# USB_Adapter_V1.net
KiCad netlist of a schematic drawn in EAGLE
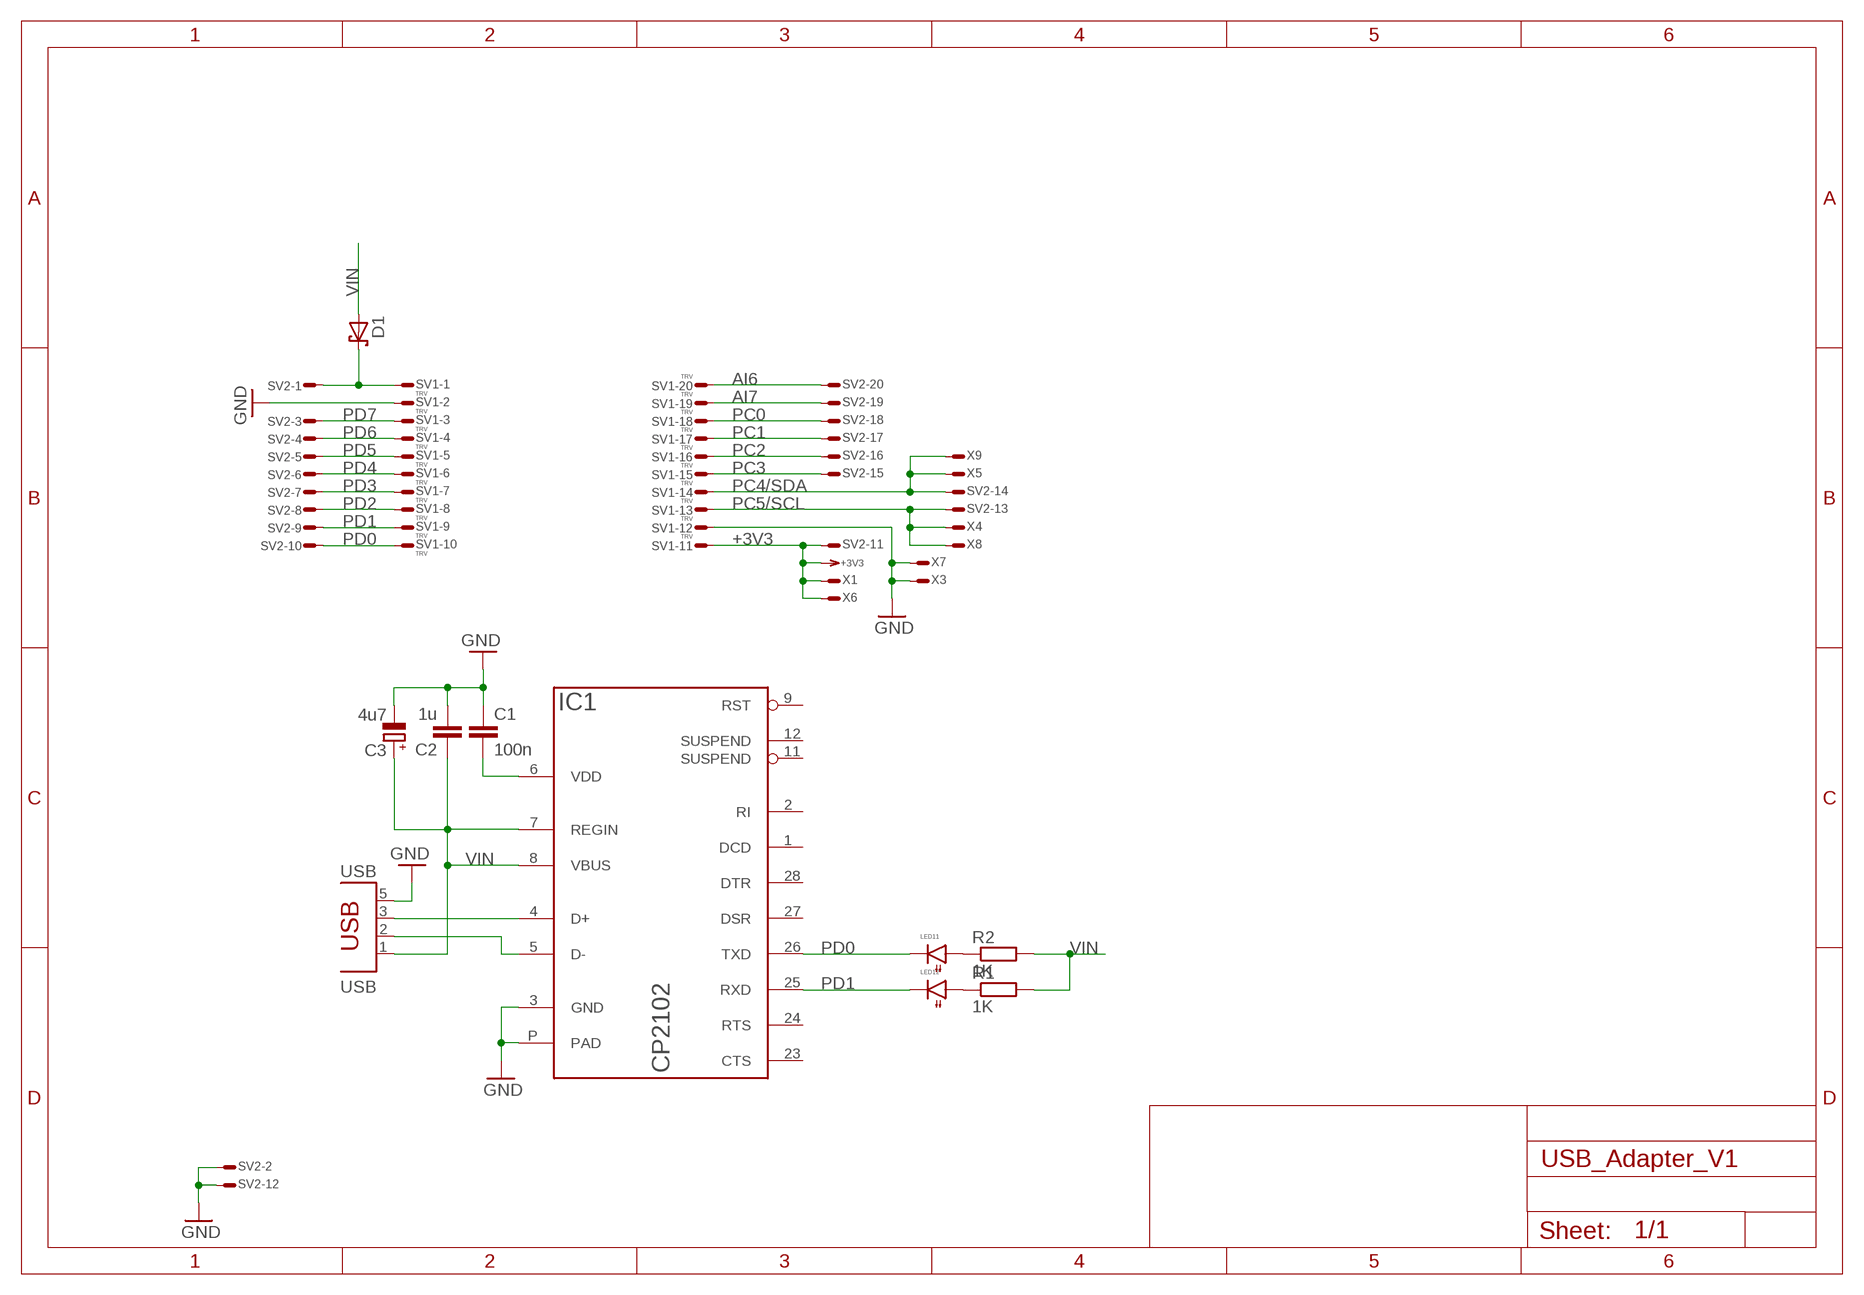
[diagram p0: schematic, sheet 1]

(export (version "E")
  (design (tool "Eeschema 10.0.6"))
  (components
    (comp (ref "C1")
      (value "100n")
      (footprint "eagle-import:0603")
      (libsource (lib "eagle-import") (part "C0603"))
    )
    (comp (ref "C2")
      (value "1u")
      (footprint "eagle-import:0603")
      (libsource (lib "eagle-import") (part "C0603"))
    )
    (comp (ref "C3")
      (value "4u7")
      (footprint "eagle-import:SMC_A")
      (libsource (lib "eagle-import") (part "C_POLSMCA"))
    )
    (comp (ref "D1")
      (value "D-SCHOTKY323")
      (footprint "eagle-import:SOD323")
      (libsource (lib "eagle-import") (part "D-SCHOTKY323"))
    )
    (comp (ref "IC1")
      (value "CP2102")
      (footprint "eagle-import:QFN28")
      (libsource (lib "eagle-import") (part "CP2102"))
    )
    (comp (ref "LED1")
      (value "2LED3")
      (footprint "eagle-import:HSMF")
      (libsource (lib "eagle-import") (part "2LED3"))
    )
    (comp (ref "R1")
      (value "1K")
      (footprint "eagle-import:0603")
      (libsource (lib "eagle-import") (part "R0603"))
    )
    (comp (ref "R2")
      (value "1K")
      (footprint "eagle-import:0603")
      (libsource (lib "eagle-import") (part "R0603"))
    )
    (comp (ref "SV1")
      (value "TRV")
      (footprint "eagle-import:FE10-2WSS")
      (libsource (lib "eagle-import") (part "FE20ELSS"))
    )
    (comp (ref "SV2")
      (value "ML20SE")
      (footprint "eagle-import:ML20S")
      (libsource (lib "eagle-import") (part "ML20?ES"))
    )
    (comp (ref "USB")
      (value "USB")
      (footprint "eagle-import:USB-BM")
      (libsource (lib "eagle-import") (part "USBBM"))
    )
    (comp (ref "X1")
      (value "WIREPADT1.6/0.9")
      (footprint "eagle-import:T1.6_0.9")
      (libsource (lib "eagle-import") (part "WIREPADT1.6/0.9"))
    )
    (comp (ref "X3")
      (value "WIREPADT1.6/0.9")
      (footprint "eagle-import:T1.6_0.9")
      (libsource (lib "eagle-import") (part "WIREPADT1.6/0.9"))
    )
    (comp (ref "X4")
      (value "WIREPADT1.6/0.9")
      (footprint "eagle-import:T1.6_0.9")
      (libsource (lib "eagle-import") (part "WIREPADT1.6/0.9"))
    )
    (comp (ref "X5")
      (value "WIREPADT1.6/0.9")
      (footprint "eagle-import:T1.6_0.9")
      (libsource (lib "eagle-import") (part "WIREPADT1.6/0.9"))
    )
    (comp (ref "X6")
      (value "WIREPADT1.6/0.9")
      (footprint "eagle-import:T1.6_0.9")
      (libsource (lib "eagle-import") (part "WIREPADT1.6/0.9"))
    )
    (comp (ref "X7")
      (value "WIREPADT1.6/0.9")
      (footprint "eagle-import:T1.6_0.9")
      (libsource (lib "eagle-import") (part "WIREPADT1.6/0.9"))
    )
    (comp (ref "X8")
      (value "WIREPADT1.6/0.9")
      (footprint "eagle-import:T1.6_0.9")
      (libsource (lib "eagle-import") (part "WIREPADT1.6/0.9"))
    )
    (comp (ref "X9")
      (value "WIREPADT1.6/0.9")
      (footprint "eagle-import:T1.6_0.9")
      (libsource (lib "eagle-import") (part "WIREPADT1.6/0.9"))
    )
  )
  (nets
    (net (code "1") (name "+3V3") (class "Default")
      (node (ref "SV1") (pin "P$11") (pinfunction "S_P$11") (pintype "passive"))
      (node (ref "SV2") (pin "11") (pinfunction "S_11") (pintype "passive"))
      (node (ref "X1") (pin "1") (pinfunction "S_1") (pintype "passive"))
      (node (ref "X6") (pin "1") (pinfunction "S_1") (pintype "passive"))
    )
    (net (code "2") (name "/AI6") (class "Default")
      (node (ref "SV1") (pin "P$20") (pinfunction "S_P$20") (pintype "passive"))
      (node (ref "SV2") (pin "20") (pinfunction "S_20") (pintype "passive"))
    )
    (net (code "3") (name "/AI7") (class "Default")
      (node (ref "SV1") (pin "P$19") (pinfunction "S_P$19") (pintype "passive"))
      (node (ref "SV2") (pin "19") (pinfunction "S_19") (pintype "passive"))
    )
    (net (code "4") (name "/PC0") (class "Default")
      (node (ref "SV1") (pin "P$18") (pinfunction "S_P$18") (pintype "passive"))
      (node (ref "SV2") (pin "18") (pinfunction "S_18") (pintype "passive"))
    )
    (net (code "5") (name "/PC1") (class "Default")
      (node (ref "SV1") (pin "P$17") (pinfunction "S_P$17") (pintype "passive"))
      (node (ref "SV2") (pin "17") (pinfunction "S_17") (pintype "passive"))
    )
    (net (code "6") (name "/PC2") (class "Default")
      (node (ref "SV1") (pin "P$16") (pinfunction "S_P$16") (pintype "passive"))
      (node (ref "SV2") (pin "16") (pinfunction "S_16") (pintype "passive"))
    )
    (net (code "7") (name "/PC3") (class "Default")
      (node (ref "SV1") (pin "P$15") (pinfunction "S_P$15") (pintype "passive"))
      (node (ref "SV2") (pin "15") (pinfunction "S_15") (pintype "passive"))
    )
    (net (code "8") (name "/PC4{slash}SDA") (class "Default")
      (node (ref "SV1") (pin "P$14") (pinfunction "S_P$14") (pintype "passive"))
      (node (ref "SV2") (pin "14") (pinfunction "S_14") (pintype "passive"))
      (node (ref "X5") (pin "1") (pinfunction "S_1") (pintype "passive"))
      (node (ref "X9") (pin "1") (pinfunction "S_1") (pintype "passive"))
    )
    (net (code "9") (name "/PC5{slash}SCL") (class "Default")
      (node (ref "SV1") (pin "P$13") (pinfunction "S_P$13") (pintype "passive"))
      (node (ref "SV2") (pin "13") (pinfunction "S_13") (pintype "passive"))
      (node (ref "X4") (pin "1") (pinfunction "S_1") (pintype "passive"))
      (node (ref "X8") (pin "1") (pinfunction "S_1") (pintype "passive"))
    )
    (net (code "10") (name "/PD0") (class "Default")
      (node (ref "IC1") (pin "26") (pinfunction "TXD_26") (pintype "output"))
      (node (ref "LED1") (pin "2") (pinfunction "C_2") (pintype "bidirectional"))
      (node (ref "SV1") (pin "P$10") (pinfunction "S_P$10") (pintype "passive"))
      (node (ref "SV2") (pin "10") (pinfunction "S_10") (pintype "passive"))
    )
    (net (code "11") (name "/PD1") (class "Default")
      (node (ref "IC1") (pin "25") (pinfunction "RXD_25") (pintype "input"))
      (node (ref "LED1") (pin "4") (pinfunction "C_4") (pintype "bidirectional"))
      (node (ref "SV1") (pin "P$9") (pinfunction "S_P$9") (pintype "passive"))
      (node (ref "SV2") (pin "9") (pinfunction "S_9") (pintype "passive"))
    )
    (net (code "12") (name "/PD2") (class "Default")
      (node (ref "SV1") (pin "P$8") (pinfunction "S_P$8") (pintype "passive"))
      (node (ref "SV2") (pin "8") (pinfunction "S_8") (pintype "passive"))
    )
    (net (code "13") (name "/PD3") (class "Default")
      (node (ref "SV1") (pin "P$7") (pinfunction "S_P$7") (pintype "passive"))
      (node (ref "SV2") (pin "7") (pinfunction "S_7") (pintype "passive"))
    )
    (net (code "14") (name "/PD4") (class "Default")
      (node (ref "SV1") (pin "P$6") (pinfunction "S_P$6") (pintype "passive"))
      (node (ref "SV2") (pin "6") (pinfunction "S_6") (pintype "passive"))
    )
    (net (code "15") (name "/PD5") (class "Default")
      (node (ref "SV1") (pin "P$5") (pinfunction "S_P$5") (pintype "passive"))
      (node (ref "SV2") (pin "5") (pinfunction "S_5") (pintype "passive"))
    )
    (net (code "16") (name "/PD6") (class "Default")
      (node (ref "SV1") (pin "P$4") (pinfunction "S_P$4") (pintype "passive"))
      (node (ref "SV2") (pin "4") (pinfunction "S_4") (pintype "passive"))
    )
    (net (code "17") (name "/PD7") (class "Default")
      (node (ref "SV1") (pin "P$3") (pinfunction "S_P$3") (pintype "passive"))
      (node (ref "SV2") (pin "3") (pinfunction "S_3") (pintype "passive"))
    )
    (net (code "18") (name "/VIN") (class "Default")
      (node (ref "C2") (pin "1") (pinfunction "1_1") (pintype "passive"))
      (node (ref "C3") (pin "+") (pinfunction "+_+") (pintype "passive"))
      (node (ref "D1") (pin "A") (pinfunction "A_A") (pintype "passive"))
      (node (ref "IC1") (pin "7") (pinfunction "REGIN_7") (pintype "input"))
      (node (ref "IC1") (pin "8") (pinfunction "VBUS_8") (pintype "input"))
      (node (ref "R1") (pin "2") (pinfunction "2_2") (pintype "passive"))
      (node (ref "R2") (pin "2") (pinfunction "2_2") (pintype "passive"))
      (node (ref "USB") (pin "1") (pinfunction "VCC_1") (pintype "bidirectional"))
    )
    (net (code "19") (name "GND") (class "Default")
      (node (ref "C1") (pin "1") (pinfunction "1_1") (pintype "passive"))
      (node (ref "C2") (pin "2") (pinfunction "2_2") (pintype "passive"))
      (node (ref "C3") (pin "-") (pinfunction "-_-") (pintype "passive"))
      (node (ref "IC1") (pin "3") (pinfunction "GND_3") (pintype "power_in"))
      (node (ref "IC1") (pin "P") (pinfunction "PAD_P") (pintype "power_in"))
      (node (ref "SV1") (pin "P$12") (pinfunction "S_P$12") (pintype "passive"))
      (node (ref "SV1") (pin "P$2") (pinfunction "S_P$2") (pintype "passive"))
      (node (ref "SV2") (pin "12") (pinfunction "S_12") (pintype "passive"))
      (node (ref "SV2") (pin "2") (pinfunction "S_2") (pintype "passive"))
      (node (ref "USB") (pin "5") (pinfunction "GND_5") (pintype "bidirectional"))
      (node (ref "X3") (pin "1") (pinfunction "S_1") (pintype "passive"))
      (node (ref "X7") (pin "1") (pinfunction "S_1") (pintype "passive"))
    )
    (net (code "20") (name "Net-(IC1-D+)") (class "Default")
      (node (ref "IC1") (pin "4") (pinfunction "D+_4") (pintype "bidirectional"))
      (node (ref "USB") (pin "3") (pinfunction "D+_3") (pintype "bidirectional"))
    )
    (net (code "21") (name "Net-(IC1-D-)") (class "Default")
      (node (ref "IC1") (pin "5") (pinfunction "D-_5") (pintype "bidirectional"))
      (node (ref "USB") (pin "2") (pinfunction "D-_2") (pintype "bidirectional"))
    )
    (net (code "22") (name "Net-(IC1-VDD)") (class "Default")
      (node (ref "C1") (pin "2") (pinfunction "2_2") (pintype "passive"))
      (node (ref "IC1") (pin "6") (pinfunction "VDD_6") (pintype "passive"))
    )
    (net (code "23") (name "Net-(LED1A-A)") (class "Default")
      (node (ref "LED1") (pin "1") (pinfunction "A_1") (pintype "bidirectional"))
      (node (ref "R2") (pin "1") (pinfunction "1_1") (pintype "passive"))
    )
    (net (code "24") (name "Net-(LED1B-A)") (class "Default")
      (node (ref "LED1") (pin "3") (pinfunction "A_3") (pintype "bidirectional"))
      (node (ref "R1") (pin "1") (pinfunction "1_1") (pintype "passive"))
    )
    (net (code "25") (name "Net-(SV1A-S)") (class "Default")
      (node (ref "D1") (pin "C") (pinfunction "C_C") (pintype "passive"))
      (node (ref "SV1") (pin "P$1") (pinfunction "S_P$1") (pintype "passive"))
      (node (ref "SV2") (pin "1") (pinfunction "S_1") (pintype "passive"))
    )
    (net (code "26") (name "unconnected-(IC1-CTS-Pad23)") (class "Default")
      (node (ref "IC1") (pin "23") (pinfunction "CTS_23") (pintype "input"))
    )
    (net (code "27") (name "unconnected-(IC1-DCD-Pad1)") (class "Default")
      (node (ref "IC1") (pin "1") (pinfunction "DCD_1") (pintype "input"))
    )
    (net (code "28") (name "unconnected-(IC1-DSR-Pad27)") (class "Default")
      (node (ref "IC1") (pin "27") (pinfunction "DSR_27") (pintype "input"))
    )
    (net (code "29") (name "unconnected-(IC1-DTR-Pad28)") (class "Default")
      (node (ref "IC1") (pin "28") (pinfunction "DTR_28") (pintype "output"))
    )
    (net (code "30") (name "unconnected-(IC1-RI-Pad2)") (class "Default")
      (node (ref "IC1") (pin "2") (pinfunction "RI_2") (pintype "input"))
    )
    (net (code "31") (name "unconnected-(IC1-RST-Pad9)") (class "Default")
      (node (ref "IC1") (pin "9") (pinfunction "RST_9") (pintype "bidirectional"))
    )
    (net (code "32") (name "unconnected-(IC1-RTS-Pad24)") (class "Default")
      (node (ref "IC1") (pin "24") (pinfunction "RTS_24") (pintype "output"))
    )
    (net (code "33") (name "unconnected-(IC1-SUSPEND-Pad11)") (class "Default")
      (node (ref "IC1") (pin "11") (pinfunction "SUSPEND_11") (pintype "output"))
    )
    (net (code "34") (name "unconnected-(IC1-SUSPEND-Pad12)") (class "Default")
      (node (ref "IC1") (pin "12") (pinfunction "SUSPEND_12") (pintype "output"))
    )
  )
)
